# Sheet1.net
KiCad netlist of a schematic drawn in Altium Designer
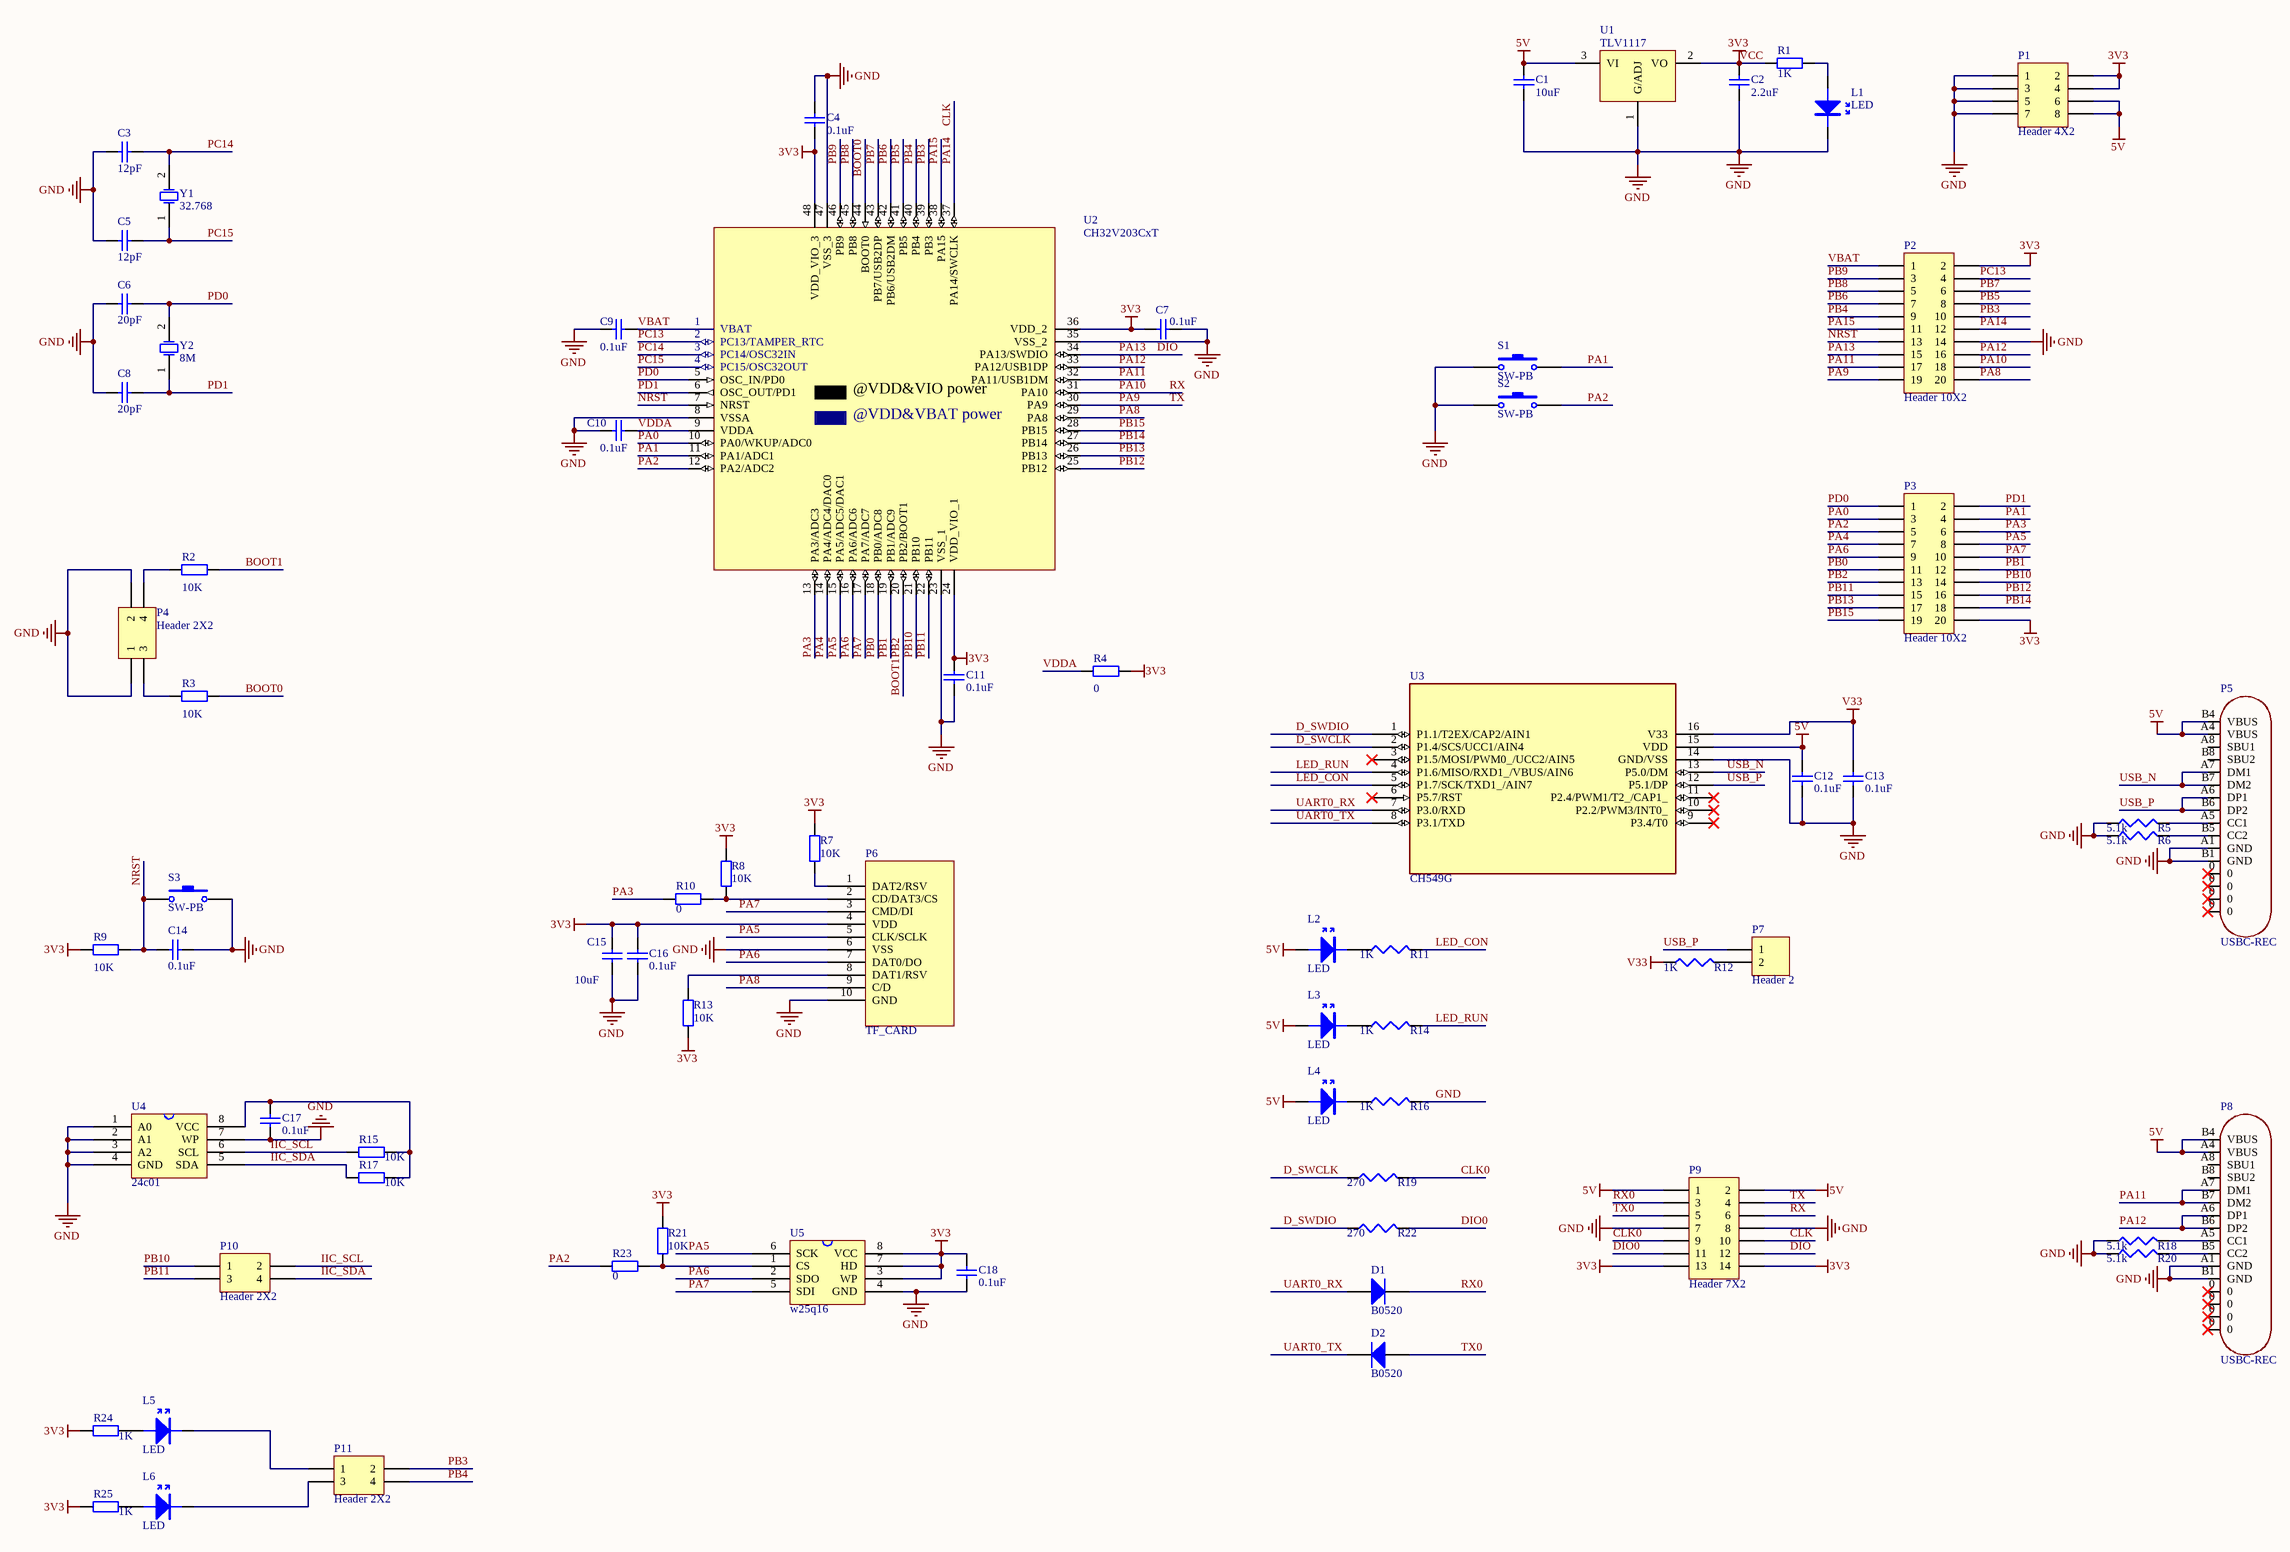
[diagram p0: Sheet1.SchDoc]

(export (version "E")
  (design (tool "Eeschema 10.0.6"))
  (components
    (comp (ref "C1")
      (value "10uF")
      (footprint "1206")
      (description "坦电容")
      (fields (field (name "PUBLISHER") "Altium Limited"))
      (libsource (lib "Miscellaneous Devices") (part "Cap"))
    )
    (comp (ref "C2")
      (value "2.2uF")
      (footprint "0805")
      (description "Capacitor")
      (fields (field (name "PUBLISHER") "Altium Limited"))
      (libsource (lib "Miscellaneous Devices") (part "Cap"))
    )
    (comp (ref "C3")
      (value "12pF")
      (footprint "0805")
      (description "Capacitor")
      (fields (field (name "PUBLISHER") "Altium Limited"))
      (libsource (lib "Miscellaneous Devices") (part "Cap"))
    )
    (comp (ref "C4")
      (value "0.1uF")
      (footprint "0805")
      (description "Capacitor")
      (fields (field (name "PUBLISHER") "Altium Limited"))
      (libsource (lib "Miscellaneous Devices") (part "Cap"))
    )
    (comp (ref "C5")
      (value "12pF")
      (footprint "0805")
      (description "Capacitor")
      (fields (field (name "PUBLISHER") "Altium Limited"))
      (libsource (lib "Miscellaneous Devices") (part "Cap"))
    )
    (comp (ref "C6")
      (value "20pF")
      (footprint "0805")
      (description "Capacitor")
      (fields (field (name "PUBLISHER") "Altium Limited"))
      (libsource (lib "Miscellaneous Devices") (part "Cap"))
    )
    (comp (ref "C7")
      (value "0.1uF")
      (footprint "0805")
      (description "Capacitor")
      (fields (field (name "PUBLISHER") "Altium Limited"))
      (libsource (lib "Miscellaneous Devices") (part "Cap"))
    )
    (comp (ref "C8")
      (value "20pF")
      (footprint "0805")
      (description "Capacitor")
      (fields (field (name "PUBLISHER") "Altium Limited"))
      (libsource (lib "Miscellaneous Devices") (part "Cap"))
    )
    (comp (ref "C9")
      (value "0.1uF")
      (footprint "0805")
      (description "Capacitor")
      (fields (field (name "Comment") "Cap") (field (name "PUBLISHER") "Altium Limited"))
      (libsource (lib "Miscellaneous Devices") (part "Cap"))
    )
    (comp (ref "C10")
      (value "0.1uF")
      (footprint "0805")
      (description "Capacitor")
      (fields (field (name "Comment") "Cap") (field (name "PUBLISHER") "Altium Limited"))
      (libsource (lib "Miscellaneous Devices") (part "Cap"))
    )
    (comp (ref "C11")
      (value "0.1uF")
      (footprint "0805")
      (description "Capacitor")
      (fields (field (name "PUBLISHER") "Altium Limited"))
      (libsource (lib "Miscellaneous Devices") (part "Cap"))
    )
    (comp (ref "C12")
      (value "0.1uF")
      (footprint "0805")
      (description "Capacitor")
      (fields (field (name "PUBLISHER") "Altium Limited"))
      (libsource (lib "Miscellaneous Devices") (part "Cap"))
    )
    (comp (ref "C13")
      (value "0.1uF")
      (footprint "0805")
      (description "Capacitor")
      (fields (field (name "PUBLISHER") "Altium Limited"))
      (libsource (lib "Miscellaneous Devices") (part "Cap"))
    )
    (comp (ref "C14")
      (value "0.1uF")
      (footprint "0805")
      (description "Capacitor")
      (fields (field (name "PUBLISHER") "Altium Limited"))
      (libsource (lib "Miscellaneous Devices") (part "Cap"))
    )
    (comp (ref "C15")
      (value "10uF")
      (footprint "0805")
      (description "Capacitor")
      (fields (field (name "PUBLISHER") "Altium Limited"))
      (libsource (lib "Miscellaneous Devices") (part "Cap"))
    )
    (comp (ref "C16")
      (value "0.1uF")
      (footprint "0805")
      (description "Capacitor")
      (fields (field (name "PUBLISHER") "Altium Limited"))
      (libsource (lib "Miscellaneous Devices") (part "Cap"))
    )
    (comp (ref "C17")
      (value "0.1uF")
      (footprint "0805")
      (description "Capacitor")
      (fields (field (name "PUBLISHER") "Altium Limited"))
      (libsource (lib "Miscellaneous Devices") (part "Cap"))
    )
    (comp (ref "C18")
      (value "0.1uF")
      (footprint "0805")
      (description "Capacitor")
      (fields (field (name "PUBLISHER") "Altium Limited"))
      (libsource (lib "Miscellaneous Devices") (part "Cap"))
    )
    (comp (ref "D1")
      (value "B0520")
      (footprint "SOD-123")
      (description "Default Diode")
      (fields (field (name "PUBLISHER") "Altium Limited"))
      (libsource (lib "Miscellaneous Devices") (part "Diode"))
    )
    (comp (ref "D2")
      (value "B0520")
      (footprint "SOD-123")
      (description "Default Diode")
      (fields (field (name "PUBLISHER") "Altium Limited"))
      (libsource (lib "Miscellaneous Devices") (part "Diode"))
    )
    (comp (ref "L1") (value "LED") (footprint "0805") (libsource (lib "CHXXX") (part "LED")))
    (comp (ref "L2") (value "LED") (footprint "0805") (libsource (lib "CHXXX") (part "LED")))
    (comp (ref "L3") (value "LED") (footprint "0805") (libsource (lib "CHXXX") (part "LED")))
    (comp (ref "L4") (value "LED") (footprint "0805") (libsource (lib "CHXXX") (part "LED")))
    (comp (ref "L5") (value "LED") (footprint "0805") (libsource (lib "CHXXX") (part "LED")))
    (comp (ref "L6") (value "LED") (footprint "0805") (libsource (lib "CHXXX") (part "LED")))
    (comp (ref "P1")
      (value "Header 4X2")
      (footprint "HDR2X4")
      (description "Header, 4-Pin, Dual row")
      (fields (field (name "PUBLISHER") "Altium Limited"))
      (libsource (lib "Miscellaneous Connectors") (part "Header 4X2"))
    )
    (comp (ref "P2")
      (value "Header 10X2")
      (footprint "HDR2X10")
      (description "Header, 10-Pin, Dual row")
      (fields (field (name "PUBLISHER") "Altium Limited"))
      (libsource (lib "Miscellaneous Connectors") (part "Header 10X2"))
    )
    (comp (ref "P3")
      (value "Header 10X2")
      (footprint "HDR2X10")
      (description "Header, 10-Pin, Dual row")
      (fields (field (name "PUBLISHER") "Altium Limited"))
      (libsource (lib "Miscellaneous Connectors") (part "Header 10X2"))
    )
    (comp (ref "P4")
      (value "Header 2X2")
      (footprint "HDR2X2")
      (description "Header, 2-Pin, Dual row")
      (fields (field (name "PUBLISHER") "Altium Limited"))
      (libsource (lib "Miscellaneous Connectors") (part "Header 2X2"))
    )
    (comp (ref "P5")
      (value "USBC-REC")
      (footprint "TYPE-C-Receptacle-2.0")
      (description "USB Type-C USB")
      (libsource (lib "CHXXX") (part "USBC-REC"))
    )
    (comp (ref "P6")
      (value "TF_CARD")
      (footprint "TF_CARD")
      (description "TF card interface")
      (libsource (lib "CHXXX") (part "TF_CARD"))
    )
    (comp (ref "P7")
      (value "Header 2")
      (footprint "HDR1X2")
      (description "Header, 2-Pin")
      (fields (field (name "PUBLISHER") "Altium Limited"))
      (libsource (lib "Miscellaneous Connectors") (part "Header 2"))
    )
    (comp (ref "P8")
      (value "USBC-REC")
      (footprint "TYPE-C-Receptacle-2.0")
      (description "USB Type-C USB")
      (libsource (lib "CHXXX") (part "USBC-REC"))
    )
    (comp (ref "P9")
      (value "Header 7X2")
      (footprint "HDR2X7")
      (description "Header, 7-Pin, Dual row")
      (fields (field (name "PUBLISHER") "Altium Limited"))
      (libsource (lib "Miscellaneous Connectors") (part "Header 7X2"))
    )
    (comp (ref "P10")
      (value "Header 2X2")
      (footprint "HDR2X2")
      (description "Header, 2-Pin, Dual row")
      (fields (field (name "PUBLISHER") "Altium Limited"))
      (libsource (lib "") (part "Header 2X2_1"))
    )
    (comp (ref "P11")
      (value "Header 2X2")
      (footprint "HDR2X2")
      (description "Header, 2-Pin, Dual row")
      (fields (field (name "PUBLISHER") "Altium Limited"))
      (libsource (lib "") (part "Header 2X2_1"))
    )
    (comp (ref "R1")
      (value "1K")
      (footprint "0805")
      (description "Resistor")
      (fields (field (name "PUBLISHER") "Altium Limited"))
      (libsource (lib "") (part "Res2_2"))
    )
    (comp (ref "R2")
      (value "10K")
      (footprint "0805")
      (description "Resistor")
      (fields (field (name "PUBLISHER") "Altium Limited"))
      (libsource (lib "") (part "Res2_1"))
    )
    (comp (ref "R3")
      (value "10K")
      (footprint "0805")
      (description "Resistor")
      (fields (field (name "PUBLISHER") "Altium Limited"))
      (libsource (lib "") (part "Res2_1"))
    )
    (comp (ref "R4")
      (value "0")
      (footprint "0805")
      (description "Resistor")
      (fields (field (name "PUBLISHER") "Altium Limited"))
      (libsource (lib "") (part "Res2_1"))
    )
    (comp (ref "R5")
      (value "5.1k")
      (footprint "0805")
      (description "Resistor")
      (fields (field (name "Comment") "5.1K") (field (name "PUBLISHER") "Altium Limited"))
      (libsource (lib "Miscellaneous Devices") (part "Res3"))
    )
    (comp (ref "R6")
      (value "5.1k")
      (footprint "0805")
      (description "Resistor")
      (fields (field (name "Comment") "5.1K") (field (name "PUBLISHER") "Altium Limited"))
      (libsource (lib "Miscellaneous Devices") (part "Res3"))
    )
    (comp (ref "R7")
      (value "10K")
      (footprint "0805")
      (description "Resistor")
      (fields (field (name "PUBLISHER") "Altium Limited"))
      (libsource (lib "Miscellaneous Devices") (part "Res2"))
    )
    (comp (ref "R8")
      (value "10K")
      (footprint "0805")
      (description "Resistor")
      (fields (field (name "PUBLISHER") "Altium Limited"))
      (libsource (lib "Miscellaneous Devices") (part "Res2"))
    )
    (comp (ref "R9")
      (value "10K")
      (footprint "0805")
      (description "Resistor")
      (fields (field (name "PUBLISHER") "Altium Limited"))
      (libsource (lib "") (part "Res2_1"))
    )
    (comp (ref "R10")
      (value "0")
      (footprint "0805")
      (description "Resistor")
      (fields (field (name "PUBLISHER") "Altium Limited"))
      (libsource (lib "") (part "Res2_2"))
    )
    (comp (ref "R11")
      (value "1K")
      (footprint "0805")
      (description "Resistor")
      (fields (field (name "PUBLISHER") "Altium Limited"))
      (libsource (lib "Miscellaneous Devices") (part "Res3"))
    )
    (comp (ref "R12")
      (value "1K")
      (footprint "0805")
      (description "Resistor")
      (fields (field (name "PUBLISHER") "Altium Limited"))
      (libsource (lib "Miscellaneous Devices") (part "Res3"))
    )
    (comp (ref "R13")
      (value "10K")
      (footprint "0805")
      (description "Resistor")
      (fields (field (name "PUBLISHER") "Altium Limited"))
      (libsource (lib "Miscellaneous Devices") (part "Res2"))
    )
    (comp (ref "R14")
      (value "1K")
      (footprint "0805")
      (description "Resistor")
      (fields (field (name "PUBLISHER") "Altium Limited"))
      (libsource (lib "Miscellaneous Devices") (part "Res3"))
    )
    (comp (ref "R15")
      (value "10K")
      (footprint "0805")
      (description "Resistor")
      (fields (field (name "PUBLISHER") "Altium Limited"))
      (libsource (lib "") (part "Res2_1"))
    )
    (comp (ref "R16")
      (value "1K")
      (footprint "0805")
      (description "Resistor")
      (fields (field (name "PUBLISHER") "Altium Limited"))
      (libsource (lib "Miscellaneous Devices") (part "Res3"))
    )
    (comp (ref "R17")
      (value "10K")
      (footprint "0805")
      (description "Resistor")
      (fields (field (name "PUBLISHER") "Altium Limited"))
      (libsource (lib "") (part "Res2_1"))
    )
    (comp (ref "R18")
      (value "5.1k")
      (footprint "0805")
      (description "Resistor")
      (fields (field (name "Comment") "5.1K") (field (name "PUBLISHER") "Altium Limited"))
      (libsource (lib "Miscellaneous Devices") (part "Res3"))
    )
    (comp (ref "R19")
      (value "270")
      (footprint "0805")
      (description "Resistor")
      (fields (field (name "PUBLISHER") "Altium Limited"))
      (libsource (lib "Miscellaneous Devices") (part "Res3"))
    )
    (comp (ref "R20")
      (value "5.1k")
      (footprint "0805")
      (description "Resistor")
      (fields (field (name "Comment") "5.1K") (field (name "PUBLISHER") "Altium Limited"))
      (libsource (lib "Miscellaneous Devices") (part "Res3"))
    )
    (comp (ref "R21")
      (value "10K")
      (footprint "0805")
      (description "Resistor")
      (fields (field (name "PUBLISHER") "Altium Limited"))
      (libsource (lib "Miscellaneous Devices") (part "Res2"))
    )
    (comp (ref "R22")
      (value "270")
      (footprint "0805")
      (description "Resistor")
      (fields (field (name "PUBLISHER") "Altium Limited"))
      (libsource (lib "Miscellaneous Devices") (part "Res3"))
    )
    (comp (ref "R23")
      (value "0")
      (footprint "0805")
      (description "Resistor")
      (fields (field (name "PUBLISHER") "Altium Limited"))
      (libsource (lib "") (part "Res2_2"))
    )
    (comp (ref "R24")
      (value "1K")
      (footprint "0805")
      (description "Resistor")
      (fields (field (name "PUBLISHER") "Altium Limited"))
      (libsource (lib "") (part "Res2_1"))
    )
    (comp (ref "R25")
      (value "1K")
      (footprint "0805")
      (description "Resistor")
      (fields (field (name "PUBLISHER") "Altium Limited"))
      (libsource (lib "") (part "Res2_1"))
    )
    (comp (ref "S1")
      (value "SW-PB")
      (footprint "sw - 3*6*2.5")
      (description "Switch")
      (fields (field (name "PUBLISHER") "Altium Limited"))
      (libsource (lib "Miscellaneous Devices") (part "SW-PB"))
    )
    (comp (ref "S2")
      (value "SW-PB")
      (footprint "sw - 3*6*2.5")
      (description "Switch")
      (fields (field (name "PUBLISHER") "Altium Limited"))
      (libsource (lib "Miscellaneous Devices") (part "SW-PB"))
    )
    (comp (ref "S3")
      (value "SW-PB")
      (footprint "sw - 3*6*2.5")
      (description "Switch")
      (fields (field (name "PUBLISHER") "Altium Limited"))
      (libsource (lib "Miscellaneous Devices") (part "SW-PB"))
    )
    (comp (ref "U1")
      (value "TLV1117")
      (footprint "SOT-223")
      (description "LDO")
      (libsource (lib "CHXXX") (part "LDO1117"))
    )
    (comp (ref "U2")
      (value "CH32V203CxT")
      (footprint "LQFP48")
      (description "RISC-V MCU,144MHz, 2*USB FS, CAN")
      (libsource (lib "CHXXX") (part "CH32V203CxT"))
    )
    (comp (ref "U3")
      (value "CH549G")
      (footprint "SOP16")
      (description "8bit MCS51 MCU with ADC & USB type-C host & device & dual UART & SPI")
      (libsource (lib "CHXXX") (part "CH549G"))
    )
    (comp (ref "U4") (value "24c01") (footprint "SOIC-8_208mil") (libsource (lib "Schlib1") (part "24c01")))
    (comp (ref "U5") (value "w25q16") (footprint "SOIC-8_208mil") (libsource (lib "Schlib1") (part "w25q16")))
    (comp (ref "Y1")
      (value "32.768")
      (footprint "XT3225")
      (description "Crystal Oscillator")
      (fields (field (name "PUBLISHER") "Altium Limited"))
      (libsource (lib "Miscellaneous Devices") (part "XTAL"))
    )
    (comp (ref "Y2")
      (value "8M")
      (footprint "XT3225")
      (description "Crystal Oscillator")
      (fields (field (name "PUBLISHER") "Altium Limited"))
      (libsource (lib "Miscellaneous Devices") (part "XTAL"))
    )
  )
  (nets
    (net (code "1") (name "/BOOT0") (class "Default")
      (node (ref "R3") (pin "2") (pinfunction "2_2") (pintype "passive"))
      (node (ref "U2") (pin "44") (pinfunction "BOOT0_44") (pintype "input"))
    )
    (net (code "2") (name "/BOOT1") (class "Default")
      (node (ref "P3") (pin "13") (pinfunction "13_13") (pintype "passive"))
      (node (ref "R2") (pin "2") (pinfunction "2_2") (pintype "passive"))
      (node (ref "U2") (pin "20") (pinfunction "PB2/BOOT1_20") (pintype "bidirectional"))
    )
    (net (code "3") (name "/CLK") (class "Default")
      (node (ref "P2") (pin "12") (pinfunction "12_12") (pintype "passive"))
      (node (ref "P9") (pin "10") (pinfunction "10_10") (pintype "passive"))
      (node (ref "U2") (pin "37") (pinfunction "PA14/SWCLK_37") (pintype "bidirectional"))
    )
    (net (code "4") (name "/CLK0") (class "Default")
      (node (ref "P9") (pin "9") (pinfunction "9_9") (pintype "passive"))
      (node (ref "R19") (pin "2") (pinfunction "2_2") (pintype "passive"))
    )
    (net (code "5") (name "/DIO") (class "Default")
      (node (ref "P2") (pin "15") (pinfunction "15_15") (pintype "passive"))
      (node (ref "P9") (pin "12") (pinfunction "12_12") (pintype "passive"))
      (node (ref "U2") (pin "34") (pinfunction "PA13/SWDIO_34") (pintype "bidirectional"))
    )
    (net (code "6") (name "/DIO0") (class "Default")
      (node (ref "P9") (pin "11") (pinfunction "11_11") (pintype "passive"))
      (node (ref "R22") (pin "2") (pinfunction "2_2") (pintype "passive"))
    )
    (net (code "7") (name "/D_SWCLK") (class "Default")
      (node (ref "R19") (pin "1") (pinfunction "1_1") (pintype "passive"))
      (node (ref "U3") (pin "2") (pinfunction "P1.4/SCS/UCC1/AIN4_2") (pintype "bidirectional"))
    )
    (net (code "8") (name "/D_SWDIO") (class "Default")
      (node (ref "R22") (pin "1") (pinfunction "1_1") (pintype "passive"))
      (node (ref "U3") (pin "1") (pinfunction "P1.1/T2EX/CAP2/AIN1_1") (pintype "bidirectional"))
    )
    (net (code "9") (name "/IIC_SCL") (class "Default")
      (node (ref "P10") (pin "2") (pinfunction "2_2") (pintype "passive"))
      (node (ref "R15") (pin "1") (pinfunction "1_1") (pintype "passive"))
      (node (ref "U4") (pin "6") (pinfunction "SCL_6") (pintype "passive"))
    )
    (net (code "10") (name "/IIC_SDA") (class "Default")
      (node (ref "P10") (pin "4") (pinfunction "4_4") (pintype "passive"))
      (node (ref "R17") (pin "1") (pinfunction "1_1") (pintype "passive"))
      (node (ref "U4") (pin "5") (pinfunction "SDA_5") (pintype "passive"))
    )
    (net (code "11") (name "/LED_CON") (class "Default")
      (node (ref "R11") (pin "2") (pinfunction "2_2") (pintype "passive"))
      (node (ref "U3") (pin "5") (pinfunction "P1.7/SCK/TXD1_/AIN7_5") (pintype "bidirectional"))
    )
    (net (code "12") (name "/LED_RUN") (class "Default")
      (node (ref "R14") (pin "2") (pinfunction "2_2") (pintype "passive"))
      (node (ref "U3") (pin "4") (pinfunction "P1.6/MISO/RXD1_/VBUS/AIN6_4") (pintype "bidirectional"))
    )
    (net (code "13") (name "/NRST") (class "Default")
      (node (ref "C14") (pin "2") (pinfunction "2_2") (pintype "passive"))
      (node (ref "P2") (pin "13") (pinfunction "13_13") (pintype "passive"))
      (node (ref "R9") (pin "2") (pinfunction "2_2") (pintype "passive"))
      (node (ref "S3") (pin "1") (pinfunction "1_1") (pintype "passive"))
      (node (ref "U2") (pin "7") (pinfunction "NRST_7") (pintype "input"))
    )
    (net (code "14") (name "/PA0") (class "Default")
      (node (ref "P3") (pin "3") (pinfunction "3_3") (pintype "passive"))
      (node (ref "U2") (pin "10") (pinfunction "PA0/WKUP/ADC0_10") (pintype "bidirectional"))
    )
    (net (code "15") (name "/PA1") (class "Default")
      (node (ref "P3") (pin "4") (pinfunction "4_4") (pintype "passive"))
      (node (ref "S1") (pin "2") (pinfunction "2_2") (pintype "passive"))
      (node (ref "U2") (pin "11") (pinfunction "PA1/ADC1_11") (pintype "bidirectional"))
    )
    (net (code "16") (name "/PA2") (class "Default")
      (node (ref "P3") (pin "5") (pinfunction "5_5") (pintype "passive"))
      (node (ref "R23") (pin "2") (pinfunction "2_2") (pintype "passive"))
      (node (ref "S2") (pin "2") (pinfunction "2_2") (pintype "passive"))
      (node (ref "U2") (pin "12") (pinfunction "PA2/ADC2_12") (pintype "bidirectional"))
    )
    (net (code "17") (name "/PA3") (class "Default")
      (node (ref "P3") (pin "6") (pinfunction "6_6") (pintype "passive"))
      (node (ref "R10") (pin "2") (pinfunction "2_2") (pintype "passive"))
      (node (ref "U2") (pin "13") (pinfunction "PA3/ADC3_13") (pintype "bidirectional"))
    )
    (net (code "18") (name "/PA4") (class "Default")
      (node (ref "P3") (pin "7") (pinfunction "7_7") (pintype "passive"))
      (node (ref "U2") (pin "14") (pinfunction "PA4/ADC4/DAC0_14") (pintype "bidirectional"))
    )
    (net (code "19") (name "/PA5") (class "Default")
      (node (ref "P3") (pin "8") (pinfunction "8_8") (pintype "passive"))
      (node (ref "P6") (pin "5") (pinfunction "CLK/SCLK_5") (pintype "passive"))
      (node (ref "U2") (pin "15") (pinfunction "PA5/ADC5/DAC1_15") (pintype "bidirectional"))
      (node (ref "U5") (pin "6") (pinfunction "SCK_6") (pintype "passive"))
    )
    (net (code "20") (name "/PA6") (class "Default")
      (node (ref "P3") (pin "9") (pinfunction "9_9") (pintype "passive"))
      (node (ref "P6") (pin "7") (pinfunction "DAT0/DO_7") (pintype "passive"))
      (node (ref "U2") (pin "16") (pinfunction "PA6/ADC6_16") (pintype "bidirectional"))
      (node (ref "U5") (pin "2") (pinfunction "SDO_2") (pintype "passive"))
    )
    (net (code "21") (name "/PA7") (class "Default")
      (node (ref "P3") (pin "10") (pinfunction "10_10") (pintype "passive"))
      (node (ref "P6") (pin "3") (pinfunction "CMD/DI_3") (pintype "passive"))
      (node (ref "U2") (pin "17") (pinfunction "PA7/ADC7_17") (pintype "bidirectional"))
      (node (ref "U5") (pin "5") (pinfunction "SDI_5") (pintype "passive"))
    )
    (net (code "22") (name "/PA8") (class "Default")
      (node (ref "P2") (pin "20") (pinfunction "20_20") (pintype "passive"))
      (node (ref "P6") (pin "9") (pinfunction "C/D_9") (pintype "passive"))
      (node (ref "U2") (pin "29") (pinfunction "PA8_29") (pintype "bidirectional"))
    )
    (net (code "23") (name "/PA9") (class "Default")
      (node (ref "P2") (pin "19") (pinfunction "19_19") (pintype "passive"))
      (node (ref "P9") (pin "4") (pinfunction "4_4") (pintype "passive"))
      (node (ref "U2") (pin "30") (pinfunction "PA9_30") (pintype "bidirectional"))
    )
    (net (code "24") (name "/PA10") (class "Default")
      (node (ref "P2") (pin "18") (pinfunction "18_18") (pintype "passive"))
      (node (ref "P9") (pin "6") (pinfunction "6_6") (pintype "passive"))
      (node (ref "U2") (pin "31") (pinfunction "PA10_31") (pintype "bidirectional"))
    )
    (net (code "25") (name "/PA11") (class "Default")
      (node (ref "P2") (pin "17") (pinfunction "17_17") (pintype "passive"))
      (node (ref "P8") (pin "A7") (pinfunction "DM1_A7") (pintype "passive"))
      (node (ref "P8") (pin "B7") (pinfunction "DM2_B7") (pintype "passive"))
      (node (ref "U2") (pin "32") (pinfunction "PA11/USB1DM_32") (pintype "bidirectional"))
    )
    (net (code "26") (name "/PA12") (class "Default")
      (node (ref "P2") (pin "16") (pinfunction "16_16") (pintype "passive"))
      (node (ref "P8") (pin "A6") (pinfunction "DP1_A6") (pintype "passive"))
      (node (ref "P8") (pin "B6") (pinfunction "DP2_B6") (pintype "passive"))
      (node (ref "U2") (pin "33") (pinfunction "PA12/USB1DP_33") (pintype "bidirectional"))
    )
    (net (code "27") (name "/PA15") (class "Default")
      (node (ref "P2") (pin "11") (pinfunction "11_11") (pintype "passive"))
      (node (ref "U2") (pin "38") (pinfunction "PA15_38") (pintype "bidirectional"))
    )
    (net (code "28") (name "/PB0") (class "Default")
      (node (ref "P3") (pin "11") (pinfunction "11_11") (pintype "passive"))
      (node (ref "U2") (pin "18") (pinfunction "PB0/ADC8_18") (pintype "bidirectional"))
    )
    (net (code "29") (name "/PB1") (class "Default")
      (node (ref "P3") (pin "12") (pinfunction "12_12") (pintype "passive"))
      (node (ref "U2") (pin "19") (pinfunction "PB1/ADC9_19") (pintype "bidirectional"))
    )
    (net (code "30") (name "/PB3") (class "Default")
      (node (ref "P11") (pin "2") (pinfunction "2_2") (pintype "passive"))
      (node (ref "P2") (pin "10") (pinfunction "10_10") (pintype "passive"))
      (node (ref "U2") (pin "39") (pinfunction "PB3_39") (pintype "bidirectional"))
    )
    (net (code "31") (name "/PB4") (class "Default")
      (node (ref "P11") (pin "4") (pinfunction "4_4") (pintype "passive"))
      (node (ref "P2") (pin "9") (pinfunction "9_9") (pintype "passive"))
      (node (ref "U2") (pin "40") (pinfunction "PB4_40") (pintype "bidirectional"))
    )
    (net (code "32") (name "/PB5") (class "Default")
      (node (ref "P2") (pin "8") (pinfunction "8_8") (pintype "passive"))
      (node (ref "U2") (pin "41") (pinfunction "PB5_41") (pintype "bidirectional"))
    )
    (net (code "33") (name "/PB6") (class "Default")
      (node (ref "P2") (pin "7") (pinfunction "7_7") (pintype "passive"))
      (node (ref "U2") (pin "42") (pinfunction "PB6/USB2DM_42") (pintype "bidirectional"))
    )
    (net (code "34") (name "/PB7") (class "Default")
      (node (ref "P2") (pin "6") (pinfunction "6_6") (pintype "passive"))
      (node (ref "U2") (pin "43") (pinfunction "PB7/USB2DP_43") (pintype "bidirectional"))
    )
    (net (code "35") (name "/PB8") (class "Default")
      (node (ref "P2") (pin "5") (pinfunction "5_5") (pintype "passive"))
      (node (ref "U2") (pin "45") (pinfunction "PB8_45") (pintype "bidirectional"))
    )
    (net (code "36") (name "/PB9") (class "Default")
      (node (ref "P2") (pin "3") (pinfunction "3_3") (pintype "passive"))
      (node (ref "U2") (pin "46") (pinfunction "PB9_46") (pintype "bidirectional"))
    )
    (net (code "37") (name "/PB10") (class "Default")
      (node (ref "P10") (pin "1") (pinfunction "1_1") (pintype "passive"))
      (node (ref "P3") (pin "14") (pinfunction "14_14") (pintype "passive"))
      (node (ref "U2") (pin "21") (pinfunction "PB10_21") (pintype "bidirectional"))
    )
    (net (code "38") (name "/PB11") (class "Default")
      (node (ref "P10") (pin "3") (pinfunction "3_3") (pintype "passive"))
      (node (ref "P3") (pin "15") (pinfunction "15_15") (pintype "passive"))
      (node (ref "U2") (pin "22") (pinfunction "PB11_22") (pintype "bidirectional"))
    )
    (net (code "39") (name "/PB12") (class "Default")
      (node (ref "P3") (pin "16") (pinfunction "16_16") (pintype "passive"))
      (node (ref "U2") (pin "25") (pinfunction "PB12_25") (pintype "bidirectional"))
    )
    (net (code "40") (name "/PB13") (class "Default")
      (node (ref "P3") (pin "17") (pinfunction "17_17") (pintype "passive"))
      (node (ref "U2") (pin "26") (pinfunction "PB13_26") (pintype "bidirectional"))
    )
    (net (code "41") (name "/PB14") (class "Default")
      (node (ref "P3") (pin "18") (pinfunction "18_18") (pintype "passive"))
      (node (ref "U2") (pin "27") (pinfunction "PB14_27") (pintype "bidirectional"))
    )
    (net (code "42") (name "/PB15") (class "Default")
      (node (ref "P3") (pin "19") (pinfunction "19_19") (pintype "passive"))
      (node (ref "U2") (pin "28") (pinfunction "PB15_28") (pintype "bidirectional"))
    )
    (net (code "43") (name "/PC13") (class "Default")
      (node (ref "P2") (pin "4") (pinfunction "4_4") (pintype "passive"))
      (node (ref "U2") (pin "2") (pinfunction "PC13/TAMPER_RTC_2") (pintype "bidirectional"))
    )
    (net (code "44") (name "/PC14") (class "Default")
      (node (ref "C3") (pin "2") (pinfunction "2_2") (pintype "passive"))
      (node (ref "U2") (pin "3") (pinfunction "PC14/OSC32IN_3") (pintype "bidirectional"))
      (node (ref "Y1") (pin "2") (pinfunction "OSC2_2") (pintype "passive"))
    )
    (net (code "45") (name "/PC15") (class "Default")
      (node (ref "C5") (pin "1") (pinfunction "1_1") (pintype "passive"))
      (node (ref "U2") (pin "4") (pinfunction "PC15/OSC32OUT_4") (pintype "bidirectional"))
      (node (ref "Y1") (pin "1") (pinfunction "OSC1_1") (pintype "passive"))
    )
    (net (code "46") (name "/PD0") (class "Default")
      (node (ref "C6") (pin "2") (pinfunction "2_2") (pintype "passive"))
      (node (ref "P3") (pin "1") (pinfunction "1_1") (pintype "passive"))
      (node (ref "U2") (pin "5") (pinfunction "OSC_IN/PD0_5") (pintype "input"))
      (node (ref "Y2") (pin "2") (pinfunction "OSC2_2") (pintype "passive"))
    )
    (net (code "47") (name "/PD1") (class "Default")
      (node (ref "C8") (pin "1") (pinfunction "1_1") (pintype "passive"))
      (node (ref "P3") (pin "2") (pinfunction "2_2") (pintype "passive"))
      (node (ref "U2") (pin "6") (pinfunction "OSC_OUT/PD1_6") (pintype "output"))
      (node (ref "Y2") (pin "1") (pinfunction "OSC1_1") (pintype "passive"))
    )
    (net (code "48") (name "/RX0") (class "Default")
      (node (ref "D1") (pin "2") (pinfunction "K_2") (pintype "passive"))
      (node (ref "P9") (pin "3") (pinfunction "3_3") (pintype "passive"))
    )
    (net (code "49") (name "/TX0") (class "Default")
      (node (ref "D2") (pin "1") (pinfunction "A_1") (pintype "passive"))
      (node (ref "P9") (pin "5") (pinfunction "5_5") (pintype "passive"))
    )
    (net (code "50") (name "/UART0_RX") (class "Default")
      (node (ref "D1") (pin "1") (pinfunction "A_1") (pintype "passive"))
      (node (ref "U3") (pin "7") (pinfunction "P3.0/RXD_7") (pintype "bidirectional"))
    )
    (net (code "51") (name "/UART0_TX") (class "Default")
      (node (ref "D2") (pin "2") (pinfunction "K_2") (pintype "passive"))
      (node (ref "U3") (pin "8") (pinfunction "P3.1/TXD_8") (pintype "bidirectional"))
    )
    (net (code "52") (name "/USB_N") (class "Default")
      (node (ref "P5") (pin "A7") (pinfunction "DM1_A7") (pintype "passive"))
      (node (ref "P5") (pin "B7") (pinfunction "DM2_B7") (pintype "passive"))
      (node (ref "U3") (pin "13") (pinfunction "P5.0/DM_13") (pintype "bidirectional"))
    )
    (net (code "53") (name "/USB_P") (class "Default")
      (node (ref "P5") (pin "A6") (pinfunction "DP1_A6") (pintype "passive"))
      (node (ref "P5") (pin "B6") (pinfunction "DP2_B6") (pintype "passive"))
      (node (ref "P7") (pin "1") (pinfunction "1_1") (pintype "passive"))
      (node (ref "U3") (pin "12") (pinfunction "P5.1/DP_12") (pintype "bidirectional"))
    )
    (net (code "54") (name "/VBAT") (class "Default")
      (node (ref "C9") (pin "2") (pinfunction "2_2") (pintype "passive"))
      (node (ref "P2") (pin "1") (pinfunction "1_1") (pintype "passive"))
      (node (ref "U2") (pin "1") (pinfunction "VBAT_1") (pintype "power_in"))
    )
    (net (code "55") (name "/VDDA") (class "Default")
      (node (ref "C10") (pin "2") (pinfunction "2_2") (pintype "passive"))
      (node (ref "R4") (pin "1") (pinfunction "1_1") (pintype "passive"))
      (node (ref "U2") (pin "9") (pinfunction "VDDA_9") (pintype "power_in"))
    )
    (net (code "56") (name "3V3") (class "Default")
      (node (ref "C11") (pin "2") (pinfunction "2_2") (pintype "passive"))
      (node (ref "C15") (pin "2") (pinfunction "2_2") (pintype "passive"))
      (node (ref "C16") (pin "2") (pinfunction "2_2") (pintype "passive"))
      (node (ref "C18") (pin "2") (pinfunction "2_2") (pintype "passive"))
      (node (ref "C2") (pin "2") (pinfunction "2_2") (pintype "passive"))
      (node (ref "C4") (pin "2") (pinfunction "2_2") (pintype "passive"))
      (node (ref "C7") (pin "2") (pinfunction "2_2") (pintype "passive"))
      (node (ref "P1") (pin "2") (pinfunction "2_2") (pintype "passive"))
      (node (ref "P1") (pin "4") (pinfunction "4_4") (pintype "passive"))
      (node (ref "P2") (pin "2") (pinfunction "2_2") (pintype "passive"))
      (node (ref "P3") (pin "20") (pinfunction "20_20") (pintype "passive"))
      (node (ref "P6") (pin "4") (pinfunction "VDD_4") (pintype "passive"))
      (node (ref "P9") (pin "13") (pinfunction "13_13") (pintype "passive"))
      (node (ref "P9") (pin "14") (pinfunction "14_14") (pintype "passive"))
      (node (ref "R1") (pin "2") (pinfunction "2_2") (pintype "passive"))
      (node (ref "R13") (pin "1") (pinfunction "1_1") (pintype "passive"))
      (node (ref "R21") (pin "2") (pinfunction "2_2") (pintype "passive"))
      (node (ref "R24") (pin "1") (pinfunction "1_1") (pintype "passive"))
      (node (ref "R25") (pin "1") (pinfunction "1_1") (pintype "passive"))
      (node (ref "R4") (pin "2") (pinfunction "2_2") (pintype "passive"))
      (node (ref "R7") (pin "2") (pinfunction "2_2") (pintype "passive"))
      (node (ref "R8") (pin "2") (pinfunction "2_2") (pintype "passive"))
      (node (ref "R9") (pin "1") (pinfunction "1_1") (pintype "passive"))
      (node (ref "U1") (pin "2") (pinfunction "VO_2") (pintype "power_in"))
      (node (ref "U2") (pin "24") (pinfunction "VDD_VIO_1_24") (pintype "power_in"))
      (node (ref "U2") (pin "36") (pinfunction "VDD_2_36") (pintype "power_in"))
      (node (ref "U2") (pin "48") (pinfunction "VDD_VIO_3_48") (pintype "power_in"))
      (node (ref "U5") (pin "3") (pinfunction "WP_3") (pintype "passive"))
      (node (ref "U5") (pin "7") (pinfunction "HD_7") (pintype "passive"))
      (node (ref "U5") (pin "8") (pinfunction "VCC_8") (pintype "passive"))
    )
    (net (code "57") (name "5V") (class "Default")
      (node (ref "C1") (pin "2") (pinfunction "2_2") (pintype "passive"))
      (node (ref "C12") (pin "2") (pinfunction "2_2") (pintype "passive"))
      (node (ref "L2") (pin "1") (pinfunction "A_1") (pintype "passive"))
      (node (ref "L3") (pin "1") (pinfunction "A_1") (pintype "passive"))
      (node (ref "L4") (pin "1") (pinfunction "A_1") (pintype "passive"))
      (node (ref "P1") (pin "6") (pinfunction "6_6") (pintype "passive"))
      (node (ref "P1") (pin "8") (pinfunction "8_8") (pintype "passive"))
      (node (ref "P5") (pin "A4") (pinfunction "VBUS_A4") (pintype "passive"))
      (node (ref "P5") (pin "B4") (pinfunction "VBUS_B4") (pintype "passive"))
      (node (ref "P8") (pin "A4") (pinfunction "VBUS_A4") (pintype "passive"))
      (node (ref "P8") (pin "B4") (pinfunction "VBUS_B4") (pintype "passive"))
      (node (ref "P9") (pin "1") (pinfunction "1_1") (pintype "passive"))
      (node (ref "P9") (pin "2") (pinfunction "2_2") (pintype "passive"))
      (node (ref "U1") (pin "3") (pinfunction "VI_3") (pintype "power_in"))
      (node (ref "U3") (pin "15") (pinfunction "VDD_15") (pintype "power_in"))
    )
    (net (code "58") (name "GND") (class "Default")
      (node (ref "C1") (pin "1") (pinfunction "1_1") (pintype "passive"))
      (node (ref "C10") (pin "1") (pinfunction "1_1") (pintype "passive"))
      (node (ref "C11") (pin "1") (pinfunction "1_1") (pintype "passive"))
      (node (ref "C12") (pin "1") (pinfunction "1_1") (pintype "passive"))
      (node (ref "C13") (pin "1") (pinfunction "1_1") (pintype "passive"))
      (node (ref "C14") (pin "1") (pinfunction "1_1") (pintype "passive"))
      (node (ref "C15") (pin "1") (pinfunction "1_1") (pintype "passive"))
      (node (ref "C16") (pin "1") (pinfunction "1_1") (pintype "passive"))
      (node (ref "C17") (pin "1") (pinfunction "1_1") (pintype "passive"))
      (node (ref "C18") (pin "1") (pinfunction "1_1") (pintype "passive"))
      (node (ref "C2") (pin "1") (pinfunction "1_1") (pintype "passive"))
      (node (ref "C3") (pin "1") (pinfunction "1_1") (pintype "passive"))
      (node (ref "C4") (pin "1") (pinfunction "1_1") (pintype "passive"))
      (node (ref "C5") (pin "2") (pinfunction "2_2") (pintype "passive"))
      (node (ref "C6") (pin "1") (pinfunction "1_1") (pintype "passive"))
      (node (ref "C7") (pin "1") (pinfunction "1_1") (pintype "passive"))
      (node (ref "C8") (pin "2") (pinfunction "2_2") (pintype "passive"))
      (node (ref "C9") (pin "1") (pinfunction "1_1") (pintype "passive"))
      (node (ref "L1") (pin "2") (pinfunction "K_2") (pintype "passive"))
      (node (ref "P1") (pin "1") (pinfunction "1_1") (pintype "passive"))
      (node (ref "P1") (pin "3") (pinfunction "3_3") (pintype "passive"))
      (node (ref "P1") (pin "5") (pinfunction "5_5") (pintype "passive"))
      (node (ref "P1") (pin "7") (pinfunction "7_7") (pintype "passive"))
      (node (ref "P2") (pin "14") (pinfunction "14_14") (pintype "passive"))
      (node (ref "P4") (pin "1") (pinfunction "1_1") (pintype "passive"))
      (node (ref "P4") (pin "2") (pinfunction "2_2") (pintype "passive"))
      (node (ref "P5") (pin "A1") (pinfunction "GND_A1") (pintype "passive"))
      (node (ref "P5") (pin "B1") (pinfunction "GND_B1") (pintype "passive"))
      (node (ref "P6") (pin "10") (pinfunction "GND_10") (pintype "passive"))
      (node (ref "P6") (pin "6") (pinfunction "VSS_6") (pintype "passive"))
      (node (ref "P8") (pin "A1") (pinfunction "GND_A1") (pintype "passive"))
      (node (ref "P8") (pin "B1") (pinfunction "GND_B1") (pintype "passive"))
      (node (ref "P9") (pin "7") (pinfunction "7_7") (pintype "passive"))
      (node (ref "P9") (pin "8") (pinfunction "8_8") (pintype "passive"))
      (node (ref "R16") (pin "2") (pinfunction "2_2") (pintype "passive"))
      (node (ref "R18") (pin "1") (pinfunction "1_1") (pintype "passive"))
      (node (ref "R20") (pin "1") (pinfunction "1_1") (pintype "passive"))
      (node (ref "R5") (pin "1") (pinfunction "1_1") (pintype "passive"))
      (node (ref "R6") (pin "1") (pinfunction "1_1") (pintype "passive"))
      (node (ref "S1") (pin "1") (pinfunction "1_1") (pintype "passive"))
      (node (ref "S2") (pin "1") (pinfunction "1_1") (pintype "passive"))
      (node (ref "S3") (pin "2") (pinfunction "2_2") (pintype "passive"))
      (node (ref "U1") (pin "1") (pinfunction "G/ADJ_1") (pintype "power_in"))
      (node (ref "U2") (pin "23") (pinfunction "VSS_1_23") (pintype "power_in"))
      (node (ref "U2") (pin "35") (pinfunction "VSS_2_35") (pintype "power_in"))
      (node (ref "U2") (pin "47") (pinfunction "VSS_3_47") (pintype "power_in"))
      (node (ref "U2") (pin "8") (pinfunction "VSSA_8") (pintype "power_in"))
      (node (ref "U3") (pin "14") (pinfunction "GND/VSS_14") (pintype "power_in"))
      (node (ref "U4") (pin "1") (pinfunction "A0_1") (pintype "passive"))
      (node (ref "U4") (pin "2") (pinfunction "A1_2") (pintype "passive"))
      (node (ref "U4") (pin "3") (pinfunction "A2_3") (pintype "passive"))
      (node (ref "U4") (pin "4") (pinfunction "GND_4") (pintype "passive"))
      (node (ref "U4") (pin "7") (pinfunction "WP_7") (pintype "passive"))
      (node (ref "U5") (pin "4") (pinfunction "GND_4") (pintype "passive"))
    )
    (net (code "59") (name "Net-(L1-A)") (class "Default")
      (node (ref "L1") (pin "1") (pinfunction "A_1") (pintype "passive"))
      (node (ref "R1") (pin "1") (pinfunction "1_1") (pintype "passive"))
    )
    (net (code "60") (name "Net-(L2-K)") (class "Default")
      (node (ref "L2") (pin "2") (pinfunction "K_2") (pintype "passive"))
      (node (ref "R11") (pin "1") (pinfunction "1_1") (pintype "passive"))
    )
    (net (code "61") (name "Net-(L3-K)") (class "Default")
      (node (ref "L3") (pin "2") (pinfunction "K_2") (pintype "passive"))
      (node (ref "R14") (pin "1") (pinfunction "1_1") (pintype "passive"))
    )
    (net (code "62") (name "Net-(L4-K)") (class "Default")
      (node (ref "L4") (pin "2") (pinfunction "K_2") (pintype "passive"))
      (node (ref "R16") (pin "1") (pinfunction "1_1") (pintype "passive"))
    )
    (net (code "63") (name "Net-(L5-A)") (class "Default")
      (node (ref "L5") (pin "1") (pinfunction "A_1") (pintype "passive"))
      (node (ref "R24") (pin "2") (pinfunction "2_2") (pintype "passive"))
    )
    (net (code "64") (name "Net-(L5-K)") (class "Default")
      (node (ref "L5") (pin "2") (pinfunction "K_2") (pintype "passive"))
      (node (ref "P11") (pin "1") (pinfunction "1_1") (pintype "passive"))
    )
    (net (code "65") (name "Net-(L6-A)") (class "Default")
      (node (ref "L6") (pin "1") (pinfunction "A_1") (pintype "passive"))
      (node (ref "R25") (pin "2") (pinfunction "2_2") (pintype "passive"))
    )
    (net (code "66") (name "Net-(L6-K)") (class "Default")
      (node (ref "L6") (pin "2") (pinfunction "K_2") (pintype "passive"))
      (node (ref "P11") (pin "3") (pinfunction "3_3") (pintype "passive"))
    )
    (net (code "67") (name "Net-(P4-Pad3)") (class "Default")
      (node (ref "P4") (pin "3") (pinfunction "3_3") (pintype "passive"))
      (node (ref "R3") (pin "1") (pinfunction "1_1") (pintype "passive"))
    )
    (net (code "68") (name "Net-(P4-Pad4)") (class "Default")
      (node (ref "P4") (pin "4") (pinfunction "4_4") (pintype "passive"))
      (node (ref "R2") (pin "1") (pinfunction "1_1") (pintype "passive"))
    )
    (net (code "69") (name "Net-(P5-CC1)") (class "Default")
      (node (ref "P5") (pin "A5") (pinfunction "CC1_A5") (pintype "passive"))
      (node (ref "R5") (pin "2") (pinfunction "2_2") (pintype "passive"))
    )
    (net (code "70") (name "Net-(P5-CC2)") (class "Default")
      (node (ref "P5") (pin "B5") (pinfunction "CC2_B5") (pintype "passive"))
      (node (ref "R6") (pin "2") (pinfunction "2_2") (pintype "passive"))
    )
    (net (code "71") (name "Net-(P6-CD{slash}DAT3{slash}CS)") (class "Default")
      (node (ref "P6") (pin "2") (pinfunction "CD/DAT3/CS_2") (pintype "passive"))
      (node (ref "R10") (pin "1") (pinfunction "1_1") (pintype "passive"))
      (node (ref "R8") (pin "1") (pinfunction "1_1") (pintype "passive"))
    )
    (net (code "72") (name "Net-(P6-DAT1{slash}RSV)") (class "Default")
      (node (ref "P6") (pin "8") (pinfunction "DAT1/RSV_8") (pintype "passive"))
      (node (ref "R13") (pin "2") (pinfunction "2_2") (pintype "passive"))
    )
    (net (code "73") (name "Net-(P6-DAT2{slash}RSV)") (class "Default")
      (node (ref "P6") (pin "1") (pinfunction "DAT2/RSV_1") (pintype "passive"))
      (node (ref "R7") (pin "1") (pinfunction "1_1") (pintype "passive"))
    )
    (net (code "74") (name "Net-(P7-Pad2)") (class "Default")
      (node (ref "P7") (pin "2") (pinfunction "2_2") (pintype "passive"))
      (node (ref "R12") (pin "2") (pinfunction "2_2") (pintype "passive"))
    )
    (net (code "75") (name "Net-(P8-CC1)") (class "Default")
      (node (ref "P8") (pin "A5") (pinfunction "CC1_A5") (pintype "passive"))
      (node (ref "R18") (pin "2") (pinfunction "2_2") (pintype "passive"))
    )
    (net (code "76") (name "Net-(P8-CC2)") (class "Default")
      (node (ref "P8") (pin "B5") (pinfunction "CC2_B5") (pintype "passive"))
      (node (ref "R20") (pin "2") (pinfunction "2_2") (pintype "passive"))
    )
    (net (code "77") (name "Net-(U4-VCC)") (class "Default")
      (node (ref "C17") (pin "2") (pinfunction "2_2") (pintype "passive"))
      (node (ref "R15") (pin "2") (pinfunction "2_2") (pintype "passive"))
      (node (ref "R17") (pin "2") (pinfunction "2_2") (pintype "passive"))
      (node (ref "U4") (pin "8") (pinfunction "VCC_8") (pintype "passive"))
    )
    (net (code "78") (name "Net-(U5-CS)") (class "Default")
      (node (ref "R21") (pin "1") (pinfunction "1_1") (pintype "passive"))
      (node (ref "R23") (pin "1") (pinfunction "1_1") (pintype "passive"))
      (node (ref "U5") (pin "1") (pinfunction "CS_1") (pintype "passive"))
    )
    (net (code "79") (name "V33") (class "Default")
      (node (ref "C13") (pin "2") (pinfunction "2_2") (pintype "passive"))
      (node (ref "R12") (pin "1") (pinfunction "1_1") (pintype "passive"))
      (node (ref "U3") (pin "16") (pinfunction "V33_16") (pintype "power_in"))
    )
    (net (code "80") (name "unconnected-(P5-Pad0)") (class "Default")
      (node (ref "P5") (pin "0") (pinfunction "0_0") (pintype "passive+no_connect"))
    )
    (net (code "81") (name "unconnected-(P5-Pad0)_1") (class "Default")
      (node (ref "P5") (pin "0") (pinfunction "0_0") (pintype "passive+no_connect"))
    )
    (net (code "82") (name "unconnected-(P5-Pad0)_2") (class "Default")
      (node (ref "P5") (pin "0") (pinfunction "0_0") (pintype "passive+no_connect"))
    )
    (net (code "83") (name "unconnected-(P5-Pad0)_3") (class "Default")
      (node (ref "P5") (pin "0") (pinfunction "0_0") (pintype "passive+no_connect"))
    )
    (net (code "84") (name "unconnected-(P5-SBU1-PadA8)") (class "Default")
      (node (ref "P5") (pin "A8") (pinfunction "SBU1_A8") (pintype "passive"))
    )
    (net (code "85") (name "unconnected-(P5-SBU2-PadB8)") (class "Default")
      (node (ref "P5") (pin "B8") (pinfunction "SBU2_B8") (pintype "passive"))
    )
    (net (code "86") (name "unconnected-(P8-Pad0)") (class "Default")
      (node (ref "P8") (pin "0") (pinfunction "0_0") (pintype "passive+no_connect"))
    )
    (net (code "87") (name "unconnected-(P8-Pad0)_1") (class "Default")
      (node (ref "P8") (pin "0") (pinfunction "0_0") (pintype "passive+no_connect"))
    )
    (net (code "88") (name "unconnected-(P8-Pad0)_2") (class "Default")
      (node (ref "P8") (pin "0") (pinfunction "0_0") (pintype "passive+no_connect"))
    )
    (net (code "89") (name "unconnected-(P8-Pad0)_3") (class "Default")
      (node (ref "P8") (pin "0") (pinfunction "0_0") (pintype "passive+no_connect"))
    )
    (net (code "90") (name "unconnected-(P8-SBU1-PadA8)") (class "Default")
      (node (ref "P8") (pin "A8") (pinfunction "SBU1_A8") (pintype "passive"))
    )
    (net (code "91") (name "unconnected-(P8-SBU2-PadB8)") (class "Default")
      (node (ref "P8") (pin "B8") (pinfunction "SBU2_B8") (pintype "passive"))
    )
    (net (code "92") (name "unconnected-(U3-P1.5{slash}MOSI{slash}PWM0_{slash}UCC2{slash}AIN5-Pad3)") (class "Default")
      (node (ref "U3") (pin "3") (pinfunction "P1.5/MOSI/PWM0_/UCC2/AIN5_3") (pintype "bidirectional+no_connect"))
    )
    (net (code "93") (name "unconnected-(U3-P2.2{slash}PWM3{slash}INT0_-Pad10)") (class "Default")
      (node (ref "U3") (pin "10") (pinfunction "P2.2/PWM3/INT0__10") (pintype "bidirectional+no_connect"))
    )
    (net (code "94") (name "unconnected-(U3-P2.4{slash}PWM1{slash}T2_{slash}CAP1_-Pad11)") (class "Default")
      (node (ref "U3") (pin "11") (pinfunction "P2.4/PWM1/T2_/CAP1__11") (pintype "bidirectional+no_connect"))
    )
    (net (code "95") (name "unconnected-(U3-P3.4{slash}T0-Pad9)") (class "Default")
      (node (ref "U3") (pin "9") (pinfunction "P3.4/T0_9") (pintype "bidirectional+no_connect"))
    )
    (net (code "96") (name "unconnected-(U3-P5.7{slash}RST-Pad6)") (class "Default")
      (node (ref "U3") (pin "6") (pinfunction "P5.7/RST_6") (pintype "input+no_connect"))
    )
  )
)
